# BP_Schematic.net
KiCad netlist of a schematic drawn in Altium Designer
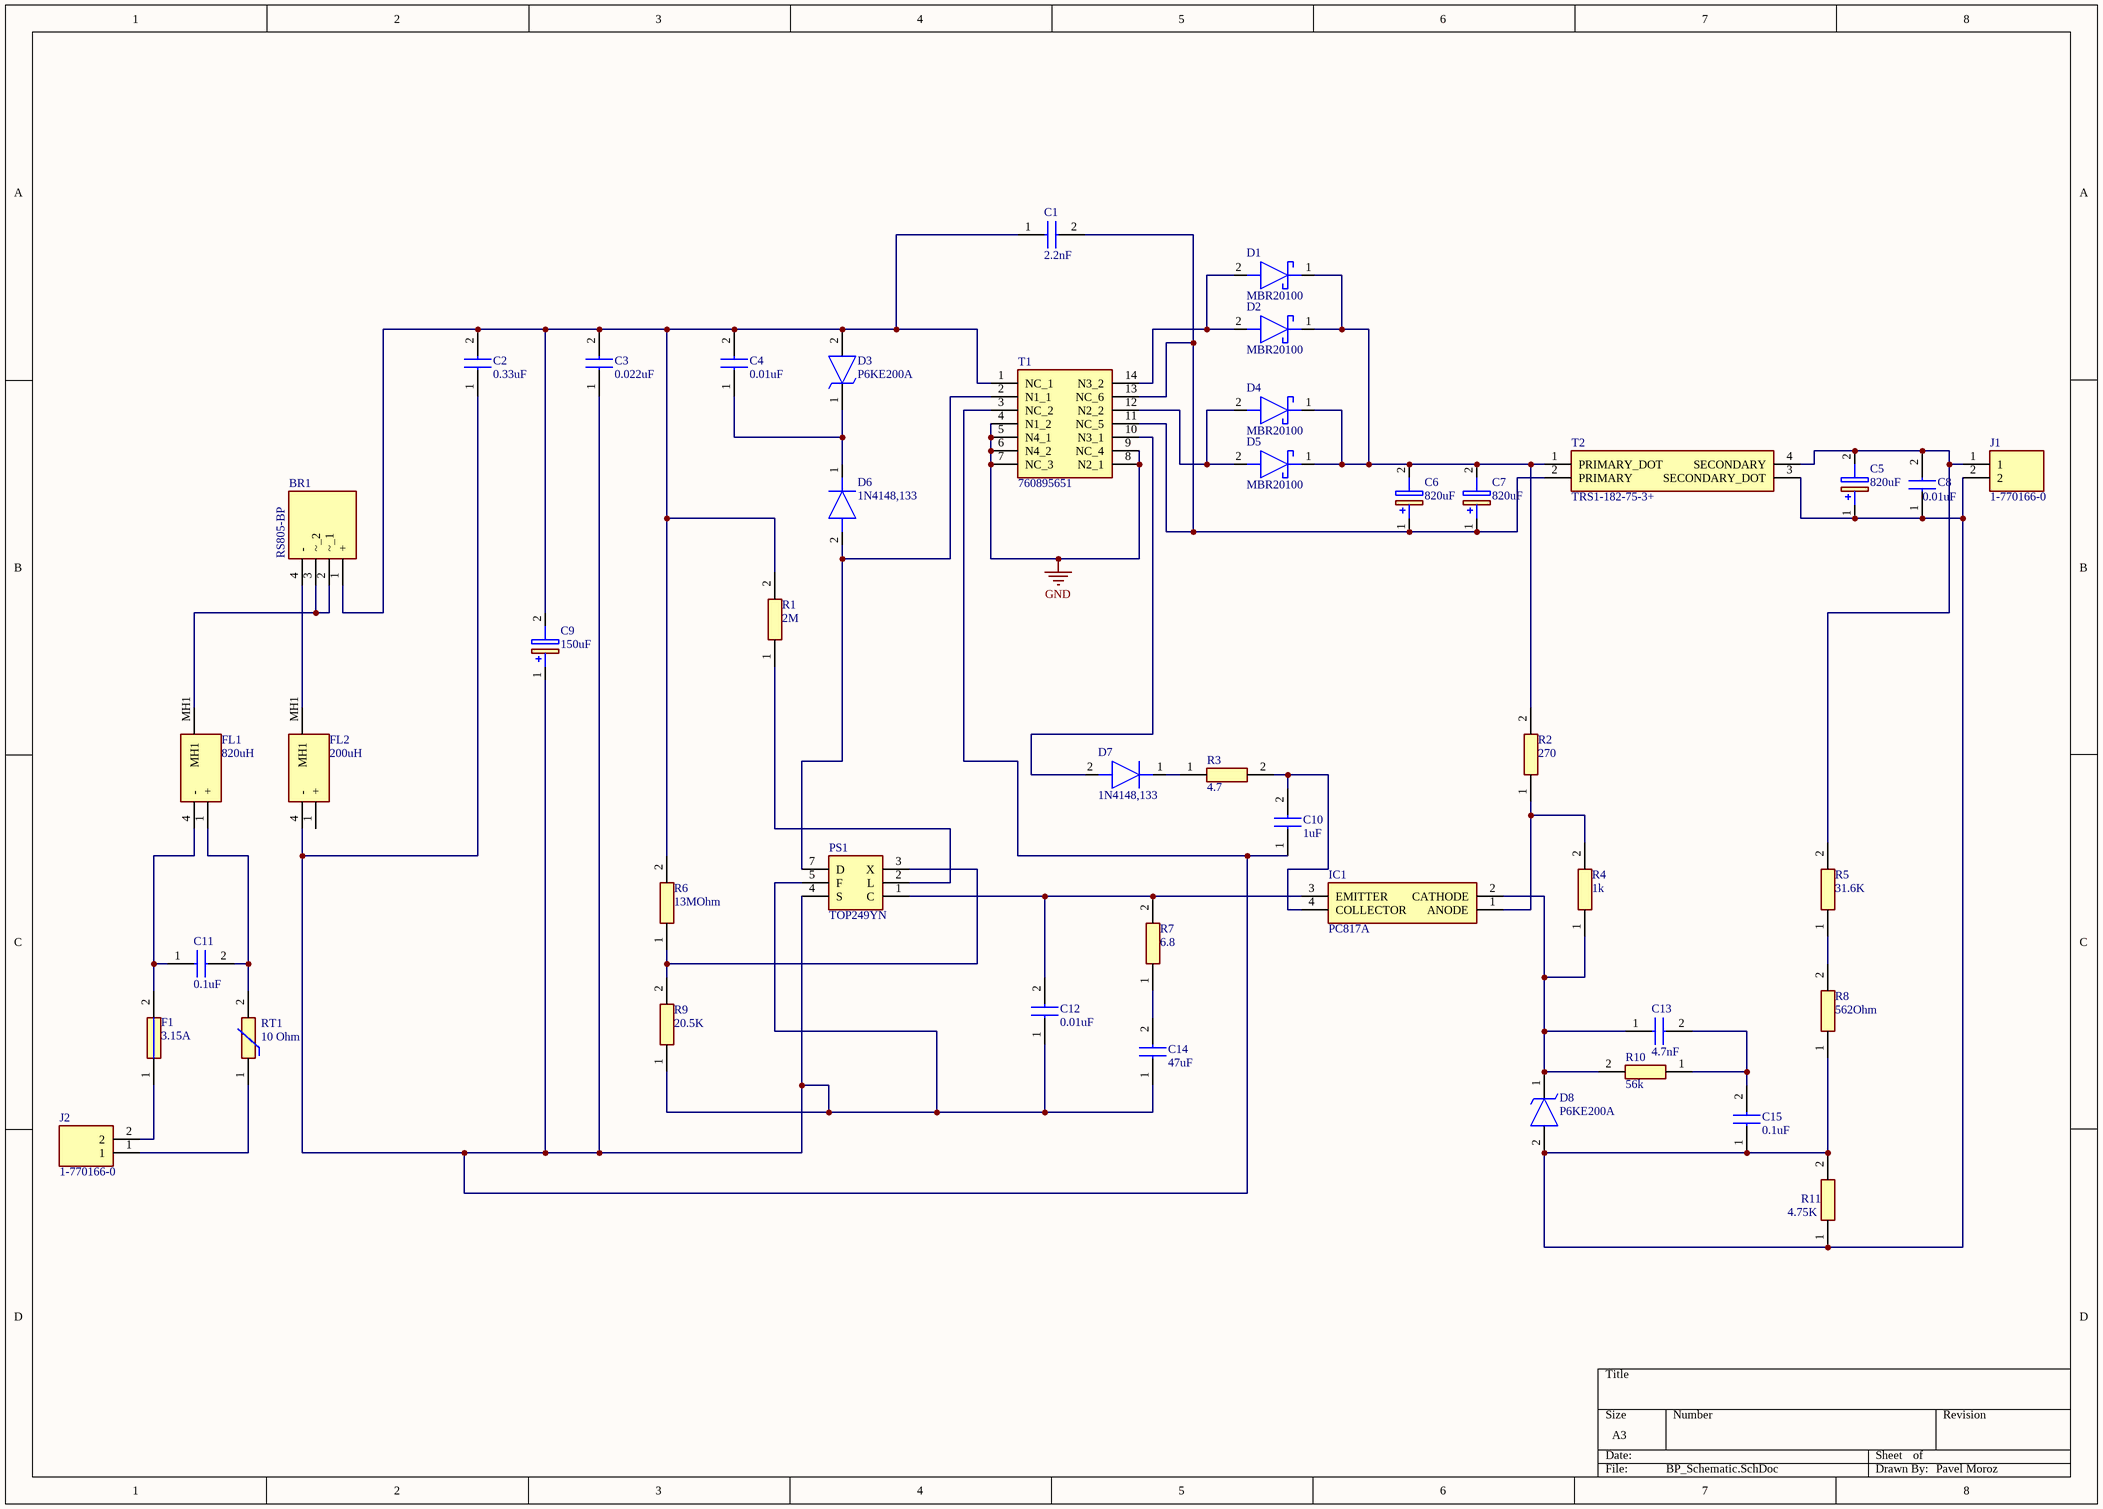
[diagram p0: BP_Schematic.SchDoc]

(export (version "E")
  (design (tool "Eeschema 10.0.6"))
  (components
    (comp (ref "BR1")
      (value "RS805-BP")
      (footprint "SamacSys:RS805BP")
      (description "Bridge Rectifier")
      (libsource (lib "*") (part "RS805-BP"))
    )
    (comp (ref "C1")
      (value "2.2nF")
      (footprint "SamacSys:GRM21x")
      (description "Capacitor")
      (fields
        (field (name "MANUFACTURER_PART_NUMBER") "GRM21A5C2E222FWA1J")
        (field (name "MOUSER PART NUMBER") "81-RM21A5C2E222FWA1J")
      )
      (libsource (lib "*") (part "GRM21A5C2E222FWA1J"))
    )
    (comp (ref "C2")
      (value "0.33uF")
      (footprint "SamacSys:CAPC9863X510N")
      (description "Capacitor")
      (fields
        (field (name "MANUFACTURER_PART_NUMBER") "ECW-U2334KCV")
        (field (name "MOUSER PART NUMBER") "667-ECW-U2334KCV")
      )
      (libsource (lib "*") (part "ECW-U2334KCV"))
    )
    (comp (ref "C3")
      (value "0.022uF")
      (footprint "SamacSys:ECHU_E1_E2_E3_E3a_4")
      (description "Capacitor")
      (fields
        (field (name "MANUFACTURER_PART_NUMBER") "ECW-U2223JC9")
        (field (name "MOUSER PART NUMBER") "667-ECW-U2223JC9")
      )
      (libsource (lib "*") (part "ECW-U2223JC9"))
    )
    (comp (ref "C4")
      (value "0.01uF")
      (footprint "SamacSys:GRM21x")
      (description "Capacitor")
      (fields
        (field (name "MANUFACTURER_PART_NUMBER") "GRM21A5C2E222FWA1J")
        (field (name "MOUSER PART NUMBER") "81-RM21A5C2E222FWA1J")
      )
      (libsource (lib "*") (part "GRM21A5C2E222FWA1J"))
    )
    (comp (ref "C5")
      (value "820uF")
      (footprint "SamacSys:T520H")
      (description "Capacitor Polarised")
      (fields
        (field (name "MANUFACTURER_PART_NUMBER") "T520H827M010ATE070")
        (field (name "MOUSER PART NUMBER") "80-T520H827M010ATE70")
      )
      (libsource (lib "*") (part "T520H827M010ATE070"))
    )
    (comp (ref "C6")
      (value "820uF")
      (footprint "SamacSys:T520H")
      (description "Capacitor Polarised")
      (fields
        (field (name "MANUFACTURER_PART_NUMBER") "T520H827M010ATE070")
        (field (name "MOUSER PART NUMBER") "80-T520H827M010ATE70")
      )
      (libsource (lib "*") (part "T520H827M010ATE070"))
    )
    (comp (ref "C7")
      (value "820uF")
      (footprint "SamacSys:T520H")
      (description "Capacitor Polarised")
      (fields
        (field (name "MANUFACTURER_PART_NUMBER") "T520H827M010ATE070")
        (field (name "MOUSER PART NUMBER") "80-T520H827M010ATE70")
      )
      (libsource (lib "*") (part "T520H827M010ATE070"))
    )
    (comp (ref "C8")
      (value "0.01uF")
      (footprint "SamacSys:GRM21x")
      (description "Capacitor")
      (fields
        (field (name "MANUFACTURER_PART_NUMBER") "GRM21A5C2E222FWA1J")
        (field (name "MOUSER PART NUMBER") "81-RM21A5C2E222FWA1J")
      )
      (libsource (lib "*") (part "GRM21A5C2E222FWA1J"))
    )
    (comp (ref "C9")
      (value "150uF")
      (footprint "SamacSys:CAPPM7343X310N")
      (description "Capacitor Polarised")
      (fields
        (field (name "MANUFACTURER_PART_NUMBER") "593D157X0010D2TE3")
        (field (name "MOUSER PART NUMBER") "74-593D157X0010D2TE3")
      )
      (libsource (lib "*") (part "593D157X0010D2TE3"))
    )
    (comp (ref "C10")
      (value "1uF")
      (footprint "SamacSys:ECQE4105KF")
      (description "Capacitor")
      (fields
        (field (name "MANUFACTURER_PART_NUMBER") "ECQ-E4105KF")
        (field (name "MOUSER PART NUMBER") "667-ECQ-E4105KF")
      )
      (libsource (lib "*") (part "ECQ-E4105KF"))
    )
    (comp (ref "C11")
      (value "0.1uF")
      (footprint "SamacSys:CAPC2012X135N")
      (description "Capacitor")
      (fields
        (field (name "MANUFACTURER_PART_NUMBER") "MAASU21GSB7104MTCA01")
        (field (name "MOUSER PART NUMBER") "963-MAASU21GSB7104M")
      )
      (libsource (lib "*") (part "MAASU21GSB7104MTCA01"))
    )
    (comp (ref "C12")
      (value "0.01uF")
      (footprint "SamacSys:GRM21x")
      (description "Capacitor")
      (fields
        (field (name "MANUFACTURER_PART_NUMBER") "GRM21A5C2E222FWA1J")
        (field (name "MOUSER PART NUMBER") "81-RM21A5C2E222FWA1J")
      )
      (libsource (lib "*") (part "GRM21A5C2E222FWA1J"))
    )
    (comp (ref "C13")
      (value "4.7nF")
      (footprint "SamacSys:B32652_(18_x_6)")
      (description "Capacitor")
      (fields
        (field (name "MANUFACTURER_PART_NUMBER") "B32652A1472J000")
        (field (name "MOUSER PART NUMBER") "871-B32652A1472J")
      )
      (libsource (lib "*") (part "B32652A1472J000"))
    )
    (comp (ref "C14")
      (value "47uF")
      (footprint "SamacSys:KR355WD7LG274MH01L")
      (description "Capacitor")
      (fields
        (field (name "MANUFACTURER_PART_NUMBER") "KRM55WR71H476MH13L")
        (field (name "MOUSER PART NUMBER") "81-KRM55WR71H476MH13")
      )
      (libsource (lib "*") (part "KRM55WR71H476MH13L"))
    )
    (comp (ref "C15")
      (value "0.1uF")
      (footprint "SamacSys:B32652_(18_x_6)")
      (description "Capacitor")
      (fields
        (field (name "MANUFACTURER_PART_NUMBER") "B32652A1472J000")
        (field (name "MOUSER PART NUMBER") "871-B32652A1472J")
      )
      (libsource (lib "*") (part "B32652A1472J000"))
    )
    (comp (ref "D1")
      (value "MBR20100")
      (footprint "SamacSys:TO508P485X1018X1930-2P")
      (description "Schottky Diode")
      (libsource (lib "*") (part "MBR20100"))
    )
    (comp (ref "D2")
      (value "MBR20100")
      (footprint "SamacSys:TO508P485X1018X1930-2P")
      (description "Schottky Diode")
      (libsource (lib "*") (part "MBR20100"))
    )
    (comp (ref "D3")
      (value "P6KE200A")
      (footprint "SamacSys:DIOAD1936W88L640D324")
      (description "TVS Diode (Uni-directional)")
      (fields (field (name "MOUSER PART NUMBER") "511-P6KE200A"))
      (libsource (lib "*") (part "P6KE200A"))
    )
    (comp (ref "D4")
      (value "MBR20100")
      (footprint "SamacSys:TO508P485X1018X1930-2P")
      (description "Schottky Diode")
      (libsource (lib "*") (part "MBR20100"))
    )
    (comp (ref "D5")
      (value "MBR20100")
      (footprint "SamacSys:TO508P485X1018X1930-2P")
      (description "Schottky Diode")
      (libsource (lib "*") (part "MBR20100"))
    )
    (comp (ref "D6")
      (value "1N4148,133")
      (footprint "SamacSys:DIOAD1165W56L425D185")
      (description "Diode")
      (fields (field (name "MOUSER PART NUMBER") "771-1N4148,133"))
      (libsource (lib "*") (part "1N4148,133"))
    )
    (comp (ref "D7")
      (value "1N4148,133")
      (footprint "SamacSys:DIOAD1165W56L425D185")
      (description "Diode")
      (fields (field (name "MOUSER PART NUMBER") "771-1N4148,133"))
      (libsource (lib "*") (part "1N4148,133"))
    )
    (comp (ref "D8")
      (value "P6KE200A")
      (footprint "SamacSys:DIOAD1936W88L640D324")
      (description "TVS Diode (Uni-directional)")
      (fields (field (name "MOUSER PART NUMBER") "511-P6KE200A"))
      (libsource (lib "*") (part "P6KE200A"))
    )
    (comp (ref "F1")
      (value "3.15A")
      (footprint "SamacSys:FUSC12145X450N")
      (description "Fuse")
      (fields
        (field (name "MANUFACTURER_PART_NUMBER") "04643.15DR")
        (field (name "MOUSER PART NUMBER") "576-04643.15DR")
      )
      (libsource (lib "*") (part "04643.15DR"))
    )
    (comp (ref "FL1")
      (value "820uH")
      (footprint "SamacSys:DMT220038L")
      (description "Filter")
      (fields
        (field (name "MANUFACTURER_PART_NUMBER") "DMT2-200-3.8L")
        (field (name "MOUSER PART NUMBER") "994-DMT2-200-3.8L")
      )
      (libsource (lib "*") (part "DMT2-200-3.8L"))
    )
    (comp (ref "FL2")
      (value "200uH")
      (footprint "SamacSys:DMT220038L")
      (description "Filter")
      (fields
        (field (name "MANUFACTURER_PART_NUMBER") "DMT2-200-3.8L")
        (field (name "MOUSER PART NUMBER") "994-DMT2-200-3.8L")
      )
      (libsource (lib "*") (part "DMT2-200-3.8L"))
    )
    (comp (ref "IC1")
      (value "PC817A")
      (footprint "SamacSys:DIP762W60P254L458H450Q4N")
      (description "Integrated Circuit")
      (libsource (lib "*") (part "PC817A"))
    )
    (comp (ref "J1")
      (value "1-770166-0")
      (footprint "SamacSys:17701660")
      (description "Connector")
      (fields (field (name "MOUSER PART NUMBER") "571-1-770166-0"))
      (libsource (lib "*") (part "1-770166-0"))
    )
    (comp (ref "J2")
      (value "1-770166-0")
      (footprint "SamacSys:17701660")
      (description "Connector")
      (fields (field (name "MOUSER PART NUMBER") "571-1-770166-0"))
      (libsource (lib "") (part "1-770166-0_1"))
    )
    (comp (ref "PS1")
      (value "TOP249YN")
      (footprint "SamacSys:TOP249YN")
      (description "Power Supply")
      (fields (field (name "MOUSER PART NUMBER") "869-TOP249YN"))
      (libsource (lib "*") (part "TOP249YN"))
    )
    (comp (ref "R1")
      (value "2M")
      (footprint "SamacSys:ERA2AED122X")
      (description "Resistor")
      (fields
        (field (name "MANUFACTURER_PART_NUMBER") "ERA-2ARB271X")
        (field (name "MOUSER PART NUMBER") "667-ERA-2ARB271X")
      )
      (libsource (lib "*") (part "ERA-2ARB271X"))
    )
    (comp (ref "R2")
      (value "270")
      (footprint "SamacSys:ERA2AED122X")
      (description "Resistor")
      (fields
        (field (name "MANUFACTURER_PART_NUMBER") "ERA-2ARB271X")
        (field (name "MOUSER PART NUMBER") "667-ERA-2ARB271X")
      )
      (libsource (lib "*") (part "ERA-2ARB271X"))
    )
    (comp (ref "R3")
      (value "4.7")
      (footprint "SamacSys:ERA3AEB101V")
      (description "Resistor")
      (fields
        (field (name "MANUFACTURER_PART_NUMBER") "ERA-3ARB4751V")
        (field (name "MOUSER PART NUMBER") "667-ERA-3ARB4751V")
      )
      (libsource (lib "*") (part "ERA-3ARB4751V"))
    )
    (comp (ref "R4")
      (value "1k")
      (footprint "SamacSys:ERJUP6")
      (description "Resistor")
      (fields (field (name "MANUFACTURER_PART_NUMBER") "ERJ-UP6F5620V"))
      (libsource (lib "*") (part "ERJ-UP6F5620V"))
    )
    (comp (ref "R5")
      (value "31.6K")
      (footprint "SamacSys:RESC1005X37N")
      (description "Resistor")
      (fields (field (name "MANUFACTURER_PART_NUMBER") "MCS04020C3162FE000"))
      (libsource (lib "*") (part "MCS04020C3162FE000"))
    )
    (comp (ref "R6")
      (value "13MOhm")
      (footprint "SamacSys:RESC1608X55N")
      (description "Resistor")
      (fields
        (field (name "MANUFACTURER_PART_NUMBER") "RK73B1JTTDD136J")
        (field (name "MOUSER PART NUMBER") "660-RK73B1JTTDD136J")
      )
      (libsource (lib "*") (part "RK73B1JTTDD136J"))
    )
    (comp (ref "R7")
      (value "6.8")
      (footprint "SamacSys:ERA3AEB101V")
      (description "Resistor")
      (fields
        (field (name "MANUFACTURER_PART_NUMBER") "ERA-3ARB4751V")
        (field (name "MOUSER PART NUMBER") "667-ERA-3ARB4751V")
      )
      (libsource (lib "") (part "ERA-3ARB4751V_1"))
    )
    (comp (ref "R8")
      (value "562Ohm")
      (footprint "SamacSys:ERJUP6")
      (description "Resistor")
      (fields (field (name "MANUFACTURER_PART_NUMBER") "ERJ-UP6F5620V"))
      (libsource (lib "*") (part "ERJ-UP6F5620V"))
    )
    (comp (ref "R9")
      (value "20.5K")
      (footprint "SamacSys:ERA2AED122X")
      (description "Resistor")
      (fields (field (name "MANUFACTURER_PART_NUMBER") "ERA-2ARB2052X"))
      (libsource (lib "*") (part "ERA-2ARB2052X"))
    )
    (comp (ref "R10")
      (value "56k")
      (footprint "SamacSys:ERJUP6")
      (description "Resistor")
      (fields (field (name "MANUFACTURER_PART_NUMBER") "ERJ-UP6F5620V"))
      (libsource (lib "") (part "ERJ-UP6F5620V_1"))
    )
    (comp (ref "R11")
      (value "4.75K")
      (footprint "SamacSys:ERA3AEB101V")
      (description "Resistor")
      (fields
        (field (name "MANUFACTURER_PART_NUMBER") "ERA-3ARB4751V")
        (field (name "MOUSER PART NUMBER") "667-ERA-3ARB4751V")
      )
      (libsource (lib "") (part "ERA-3ARB4751V_1"))
    )
    (comp (ref "RT1")
      (value "10 Ohm")
      (footprint "SamacSys:10D207LD")
      (description "Thermistor")
      (fields
        (field (name "MANUFACTURER_PART_NUMBER") "10D2-07LD")
        (field (name "MOUSER PART NUMBER") "954-10D2-07LD")
      )
      (libsource (lib "*") (part "10D2-07LD"))
    )
    (comp (ref "T1")
      (value "760895651")
      (footprint "SamacSys:760895651")
      (description "Transformer")
      (fields (field (name "MOUSER PART NUMBER") "710-760895651"))
      (libsource (lib "*") (part "760895651"))
    )
    (comp (ref "T2")
      (value "TRS1-182-75-3+")
      (footprint "SamacSys:TRS1182753")
      (description "Transformer")
      (fields (field (name "MOUSER PART NUMBER") "139-TRS1-182-75-3+"))
      (libsource (lib "*") (part "TRS1-182-75-3+"))
    )
  )
  (nets
    (net (code "1") (name "GND") (class "Default")
      (node (ref "T1") (pin "4") (pinfunction "N1_2_4") (pintype "passive"))
      (node (ref "T1") (pin "5") (pinfunction "N4_1_5") (pintype "passive"))
      (node (ref "T1") (pin "6") (pinfunction "N4_2_6") (pintype "passive"))
      (node (ref "T1") (pin "7") (pinfunction "NC_3_7") (pintype "passive"))
      (node (ref "T1") (pin "8") (pinfunction "N2_1_8") (pintype "passive"))
      (node (ref "T1") (pin "9") (pinfunction "NC_4_9") (pintype "passive"))
    )
    (net (code "2") (name "Net-(BR1-+)") (class "Default")
      (node (ref "BR1") (pin "1") (pinfunction "+_1") (pintype "passive"))
      (node (ref "C1") (pin "1") (pinfunction "1_1") (pintype "passive"))
      (node (ref "C2") (pin "2") (pinfunction "2_2") (pintype "passive"))
      (node (ref "C3") (pin "2") (pinfunction "2_2") (pintype "passive"))
      (node (ref "C4") (pin "2") (pinfunction "2_2") (pintype "passive"))
      (node (ref "C9") (pin "2") (pinfunction "-_2") (pintype "passive"))
      (node (ref "D3") (pin "2") (pinfunction "A_2") (pintype "passive"))
      (node (ref "R1") (pin "2") (pinfunction "2_2") (pintype "passive"))
      (node (ref "R6") (pin "2") (pinfunction "2_2") (pintype "passive"))
      (node (ref "T1") (pin "1") (pinfunction "NC_1_1") (pintype "passive"))
    )
    (net (code "3") (name "Net-(BR1--)") (class "Default")
      (node (ref "BR1") (pin "4") (pinfunction "-_4") (pintype "passive"))
      (node (ref "FL2") (pin "MH1") (pinfunction "MH1_MH1") (pintype "passive"))
    )
    (net (code "4") (name "Net-(BR1-~_1)") (class "Default")
      (node (ref "BR1") (pin "2") (pinfunction "~_1_2") (pintype "passive"))
      (node (ref "BR1") (pin "3") (pinfunction "~_2_3") (pintype "passive"))
      (node (ref "FL1") (pin "MH1") (pinfunction "MH1_MH1") (pintype "passive"))
    )
    (net (code "5") (name "Net-(C5-+)") (class "Default")
      (node (ref "C15") (pin "1") (pinfunction "1_1") (pintype "passive"))
      (node (ref "C5") (pin "1") (pinfunction "+_1") (pintype "passive"))
      (node (ref "C8") (pin "1") (pinfunction "1_1") (pintype "passive"))
      (node (ref "D8") (pin "2") (pinfunction "A_2") (pintype "passive"))
      (node (ref "J1") (pin "2") (pinfunction "2_2") (pintype "passive"))
      (node (ref "R11") (pin "1") (pinfunction "1_1") (pintype "passive"))
      (node (ref "R11") (pin "2") (pinfunction "2_2") (pintype "passive"))
      (node (ref "R8") (pin "1") (pinfunction "1_1") (pintype "passive"))
      (node (ref "T2") (pin "3") (pinfunction "SECONDARY_DOT_3") (pintype "passive"))
    )
    (net (code "6") (name "Net-(C5--)") (class "Default")
      (node (ref "C5") (pin "2") (pinfunction "-_2") (pintype "passive"))
      (node (ref "C8") (pin "2") (pinfunction "2_2") (pintype "passive"))
      (node (ref "J1") (pin "1") (pinfunction "1_1") (pintype "passive"))
      (node (ref "R5") (pin "2") (pinfunction "2_2") (pintype "passive"))
      (node (ref "T2") (pin "4") (pinfunction "SECONDARY_4") (pintype "passive"))
    )
    (net (code "7") (name "Net-(C6-+)") (class "Default")
      (node (ref "C1") (pin "2") (pinfunction "2_2") (pintype "passive"))
      (node (ref "C6") (pin "1") (pinfunction "+_1") (pintype "passive"))
      (node (ref "C7") (pin "1") (pinfunction "+_1") (pintype "passive"))
      (node (ref "T1") (pin "11") (pinfunction "NC_5_11") (pintype "passive"))
      (node (ref "T1") (pin "13") (pinfunction "NC_6_13") (pintype "passive"))
      (node (ref "T2") (pin "2") (pinfunction "PRIMARY_2") (pintype "passive"))
    )
    (net (code "8") (name "Net-(C6--)") (class "Default")
      (node (ref "C6") (pin "2") (pinfunction "-_2") (pintype "passive"))
      (node (ref "C7") (pin "2") (pinfunction "-_2") (pintype "passive"))
      (node (ref "D1") (pin "1") (pinfunction "K_1") (pintype "passive"))
      (node (ref "D2") (pin "1") (pinfunction "K_1") (pintype "passive"))
      (node (ref "D4") (pin "1") (pinfunction "K_1") (pintype "passive"))
      (node (ref "D5") (pin "1") (pinfunction "K_1") (pintype "passive"))
      (node (ref "R2") (pin "2") (pinfunction "2_2") (pintype "passive"))
      (node (ref "T2") (pin "1") (pinfunction "PRIMARY_DOT_1") (pintype "passive"))
    )
    (net (code "9") (name "Net-(C9-+)") (class "Default")
      (node (ref "C10") (pin "1") (pinfunction "1_1") (pintype "passive"))
      (node (ref "C12") (pin "1") (pinfunction "1_1") (pintype "passive"))
      (node (ref "C14") (pin "1") (pinfunction "1_1") (pintype "passive"))
      (node (ref "C2") (pin "1") (pinfunction "1_1") (pintype "passive"))
      (node (ref "C3") (pin "1") (pinfunction "1_1") (pintype "passive"))
      (node (ref "C9") (pin "1") (pinfunction "+_1") (pintype "passive"))
      (node (ref "FL2") (pin "4") (pinfunction "-_4") (pintype "passive"))
      (node (ref "PS1") (pin "4") (pinfunction "S_4") (pintype "passive"))
      (node (ref "PS1") (pin "5") (pinfunction "F_5") (pintype "passive"))
      (node (ref "R9") (pin "1") (pinfunction "1_1") (pintype "passive"))
      (node (ref "T1") (pin "3") (pinfunction "NC_2_3") (pintype "passive"))
    )
    (net (code "10") (name "Net-(C13-Pad2)") (class "Default")
      (node (ref "C13") (pin "2") (pinfunction "2_2") (pintype "passive"))
      (node (ref "C15") (pin "2") (pinfunction "2_2") (pintype "passive"))
      (node (ref "R10") (pin "1") (pinfunction "1_1") (pintype "passive"))
    )
    (net (code "11") (name "Net-(C14-Pad2)") (class "Default")
      (node (ref "C14") (pin "2") (pinfunction "2_2") (pintype "passive"))
      (node (ref "R7") (pin "1") (pinfunction "1_1") (pintype "passive"))
    )
    (net (code "12") (name "Net-(D1-A)") (class "Default")
      (node (ref "D1") (pin "2") (pinfunction "A_2") (pintype "passive"))
      (node (ref "D2") (pin "2") (pinfunction "A_2") (pintype "passive"))
      (node (ref "T1") (pin "14") (pinfunction "N3_2_14") (pintype "passive"))
    )
    (net (code "13") (name "Net-(D3-K)") (class "Default")
      (node (ref "C4") (pin "1") (pinfunction "1_1") (pintype "passive"))
      (node (ref "D3") (pin "1") (pinfunction "K_1") (pintype "passive"))
      (node (ref "D6") (pin "1") (pinfunction "K_1") (pintype "passive"))
    )
    (net (code "14") (name "Net-(D4-A)") (class "Default")
      (node (ref "D4") (pin "2") (pinfunction "A_2") (pintype "passive"))
      (node (ref "D5") (pin "2") (pinfunction "A_2") (pintype "passive"))
      (node (ref "T1") (pin "12") (pinfunction "N2_2_12") (pintype "passive"))
    )
    (net (code "15") (name "Net-(D6-A)") (class "Default")
      (node (ref "D6") (pin "2") (pinfunction "A_2") (pintype "passive"))
      (node (ref "PS1") (pin "7") (pinfunction "D_7") (pintype "passive"))
      (node (ref "T1") (pin "2") (pinfunction "N1_1_2") (pintype "passive"))
    )
    (net (code "16") (name "Net-(D7-A)") (class "Default")
      (node (ref "D7") (pin "2") (pinfunction "A_2") (pintype "passive"))
      (node (ref "T1") (pin "10") (pinfunction "N3_1_10") (pintype "passive"))
    )
    (net (code "17") (name "Net-(D7-K)") (class "Default")
      (node (ref "D7") (pin "1") (pinfunction "K_1") (pintype "passive"))
      (node (ref "R3") (pin "1") (pinfunction "1_1") (pintype "passive"))
    )
    (net (code "18") (name "Net-(D8-K)") (class "Default")
      (node (ref "C13") (pin "1") (pinfunction "1_1") (pintype "passive"))
      (node (ref "D8") (pin "1") (pinfunction "K_1") (pintype "passive"))
      (node (ref "IC1") (pin "2") (pinfunction "CATHODE_2") (pintype "passive"))
      (node (ref "R10") (pin "2") (pinfunction "2_2") (pintype "passive"))
      (node (ref "R4") (pin "1") (pinfunction "1_1") (pintype "passive"))
    )
    (net (code "19") (name "Net-(F1-Pad1)") (class "Default")
      (node (ref "F1") (pin "1") (pinfunction "1_1") (pintype "passive"))
      (node (ref "J2") (pin "2") (pinfunction "2_2") (pintype "passive"))
    )
    (net (code "20") (name "Net-(FL1-+)") (class "Default")
      (node (ref "C11") (pin "2") (pinfunction "2_2") (pintype "passive"))
      (node (ref "FL1") (pin "1") (pinfunction "+_1") (pintype "passive"))
      (node (ref "RT1") (pin "2") (pinfunction "2_2") (pintype "passive"))
    )
    (net (code "21") (name "Net-(FL1--)") (class "Default")
      (node (ref "C11") (pin "1") (pinfunction "1_1") (pintype "passive"))
      (node (ref "F1") (pin "2") (pinfunction "2_2") (pintype "passive"))
      (node (ref "FL1") (pin "4") (pinfunction "-_4") (pintype "passive"))
    )
    (net (code "22") (name "Net-(IC1-ANODE)") (class "Default")
      (node (ref "IC1") (pin "1") (pinfunction "ANODE_1") (pintype "passive"))
      (node (ref "R2") (pin "1") (pinfunction "1_1") (pintype "passive"))
      (node (ref "R4") (pin "2") (pinfunction "2_2") (pintype "passive"))
    )
    (net (code "23") (name "Net-(IC1-COLLECTOR)") (class "Default")
      (node (ref "C10") (pin "2") (pinfunction "2_2") (pintype "passive"))
      (node (ref "IC1") (pin "4") (pinfunction "COLLECTOR_4") (pintype "passive"))
      (node (ref "R3") (pin "2") (pinfunction "2_2") (pintype "passive"))
    )
    (net (code "24") (name "Net-(IC1-EMITTER)") (class "Default")
      (node (ref "C12") (pin "2") (pinfunction "2_2") (pintype "passive"))
      (node (ref "IC1") (pin "3") (pinfunction "EMITTER_3") (pintype "passive"))
      (node (ref "PS1") (pin "1") (pinfunction "C_1") (pintype "passive"))
      (node (ref "R7") (pin "2") (pinfunction "2_2") (pintype "passive"))
    )
    (net (code "25") (name "Net-(J2-Pad1)") (class "Default")
      (node (ref "J2") (pin "1") (pinfunction "1_1") (pintype "passive"))
      (node (ref "RT1") (pin "1") (pinfunction "1_1") (pintype "passive"))
    )
    (net (code "26") (name "Net-(PS1-L)") (class "Default")
      (node (ref "PS1") (pin "2") (pinfunction "L_2") (pintype "passive"))
      (node (ref "R1") (pin "1") (pinfunction "1_1") (pintype "passive"))
    )
    (net (code "27") (name "Net-(PS1-X)") (class "Default")
      (node (ref "PS1") (pin "3") (pinfunction "X_3") (pintype "passive"))
      (node (ref "R6") (pin "1") (pinfunction "1_1") (pintype "passive"))
      (node (ref "R9") (pin "2") (pinfunction "2_2") (pintype "passive"))
    )
    (net (code "28") (name "Net-(R5-Pad1)") (class "Default")
      (node (ref "R5") (pin "1") (pinfunction "1_1") (pintype "passive"))
      (node (ref "R8") (pin "2") (pinfunction "2_2") (pintype "passive"))
    )
    (net (code "29") (name "unconnected-(FL2-+-Pad1)") (class "Default")
      (node (ref "FL2") (pin "1") (pinfunction "+_1") (pintype "passive"))
    )
  )
)
